# power.net
KiCad netlist of a schematic drawn in Altium Designer
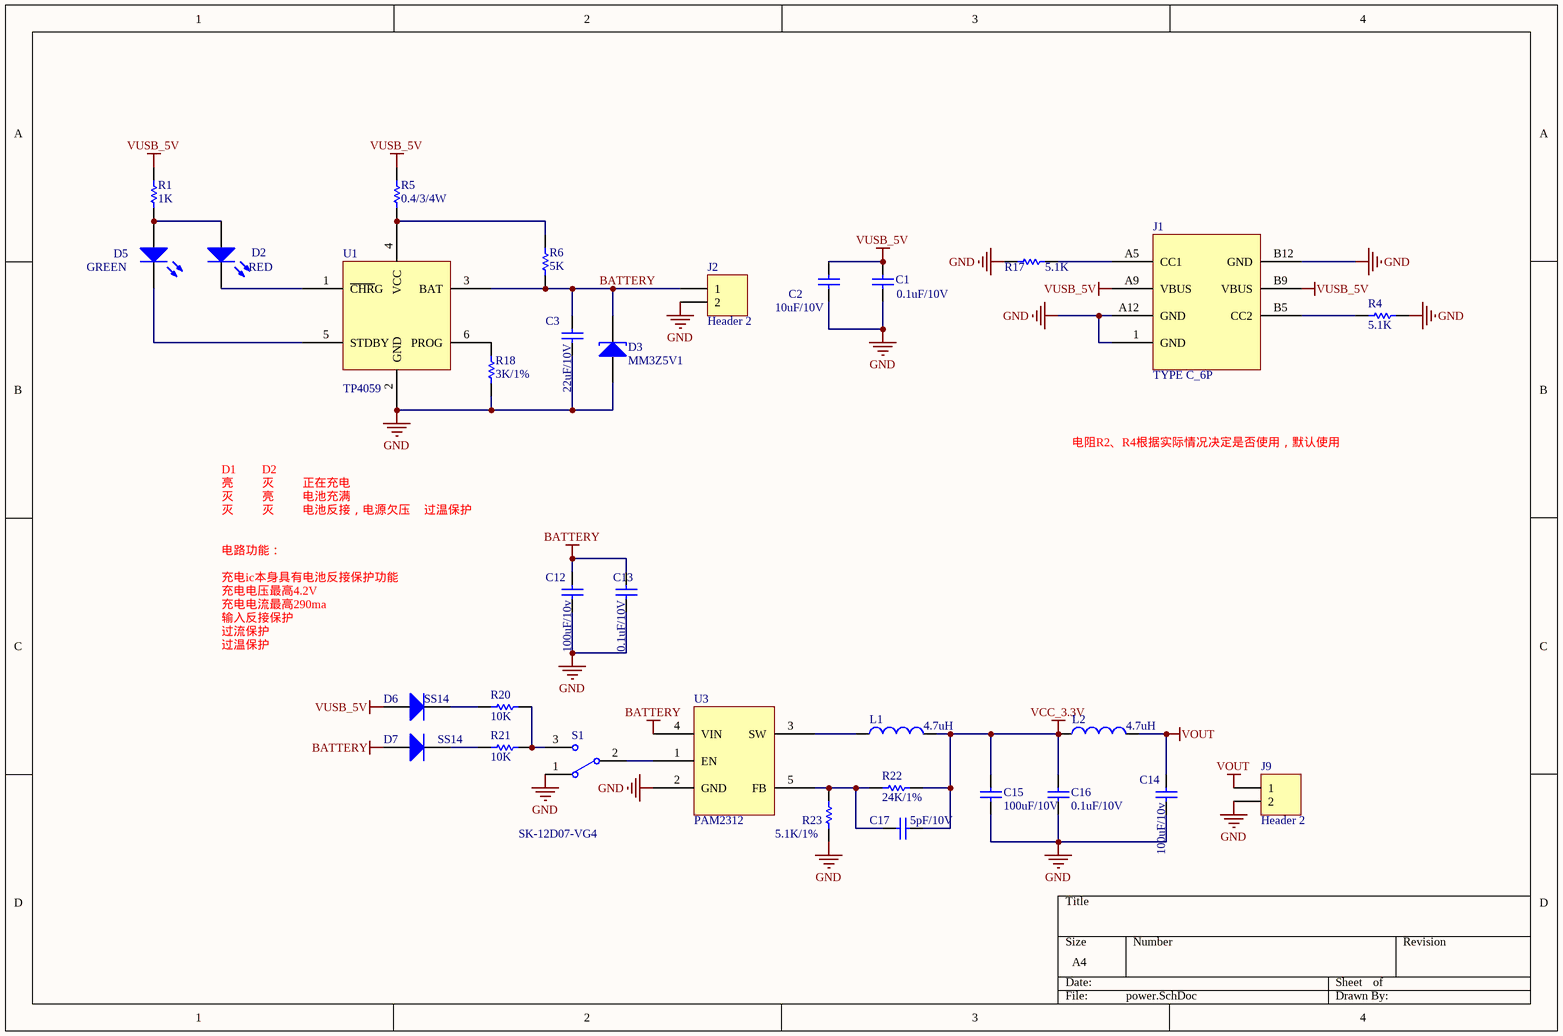
[diagram p0: power.SchDoc]

(export (version "E")
  (design (tool "Eeschema 10.0.6"))
  (components
    (comp (ref "C1")
      (value "0.1uF/10V")
      (footprint "0402C")
      (description "Capacitor")
      (fields (field (name "PUBLISHER") "Altium Limited"))
      (libsource (lib "Miscellaneous Devices") (part "Cap"))
    )
    (comp (ref "C2")
      (value "10uF/10V")
      (footprint "0603C")
      (description "Capacitor")
      (fields (field (name "PUBLISHER") "Altium Limited"))
      (libsource (lib "Miscellaneous Devices") (part "Cap"))
    )
    (comp (ref "C3")
      (value "22uF/10V")
      (footprint "1206C")
      (description "Capacitor")
      (fields (field (name "PUBLISHER") "Altium Limited"))
      (libsource (lib "Miscellaneous Devices") (part "Cap"))
    )
    (comp (ref "C12")
      (value "100uF/10v")
      (footprint "1206C")
      (description "Capacitor")
      (fields (field (name "PUBLISHER") "Altium Limited"))
      (libsource (lib "Miscellaneous Devices") (part "Cap"))
    )
    (comp (ref "C13")
      (value "0.1uF/10V")
      (footprint "0402c")
      (description "Capacitor")
      (fields (field (name "PUBLISHER") "Altium Limited"))
      (libsource (lib "Miscellaneous Devices") (part "Cap"))
    )
    (comp (ref "C14")
      (value "100uF/10v")
      (footprint "1206C")
      (description "Capacitor")
      (fields (field (name "PUBLISHER") "Altium Limited"))
      (libsource (lib "Miscellaneous Devices") (part "Cap"))
    )
    (comp (ref "C15")
      (value "100uF/10V")
      (footprint "1206C")
      (description "Capacitor")
      (fields (field (name "PUBLISHER") "Altium Limited"))
      (libsource (lib "Miscellaneous Devices") (part "Cap"))
    )
    (comp (ref "C16")
      (value "0.1uF/10V")
      (footprint "0402C")
      (description "Capacitor")
      (fields (field (name "PUBLISHER") "Altium Limited"))
      (libsource (lib "Miscellaneous Devices") (part "Cap"))
    )
    (comp (ref "C17")
      (value "5pF/10V")
      (footprint "0402C")
      (description "Capacitor")
      (fields (field (name "PUBLISHER") "Altium Limited"))
      (libsource (lib "Miscellaneous Devices") (part "Cap"))
    )
    (comp (ref "D2")
      (value "~")
      (footprint "0603LED")
      (description "Typical INFRARED GaAs LED")
      (fields (field (name "PUBLISHER") "RED"))
      (libsource (lib "Miscellaneous Devices") (part "LED0"))
    )
    (comp (ref "D3")
      (value "MM3Z5V1")
      (footprint "SOD323")
      (description "Tunnel Diode - RLC Model")
      (fields (field (name "PUBLISHER") "Altium Limited"))
      (libsource (lib "Miscellaneous Devices") (part "D Tunnel1"))
    )
    (comp (ref "D5")
      (value "~")
      (footprint "0603LED")
      (description "Typical INFRARED GaAs LED")
      (fields (field (name "PUBLISHER") "GREEN"))
      (libsource (lib "Miscellaneous Devices") (part "LED0"))
    )
    (comp (ref "D6")
      (value "SS14")
      (footprint "SMA")
      (description "Default Diode")
      (fields (field (name "PUBLISHER") "Altium Limited"))
      (libsource (lib "Miscellaneous Devices") (part "Diode"))
    )
    (comp (ref "D7")
      (value "SS14")
      (footprint "SMA")
      (description "Default Diode")
      (fields (field (name "PUBLISHER") "Altium Limited"))
      (libsource (lib "Miscellaneous Devices") (part "Diode"))
    )
    (comp (ref "J1")
      (value "TYPE C_6P")
      (footprint "TYPEC_6P")
      (libsource (lib "Schlib_20110825") (part "TYPE C_6P"))
    )
    (comp (ref "J2")
      (value "Header 2")
      (footprint "2X1.25MMZ")
      (description "Header, 2-Pin")
      (fields (field (name "PUBLISHER") "Altium Limited"))
      (libsource (lib "Miscellaneous Connectors") (part "Header 2"))
    )
    (comp (ref "J9")
      (value "Header 2")
      (footprint "HDR1X2")
      (description "Header, 2-Pin")
      (fields (field (name "PUBLISHER") "Altium Limited"))
      (libsource (lib "Miscellaneous Connectors") (part "Header 2"))
    )
    (comp (ref "L1")
      (value "4.7uH")
      (footprint "0805r")
      (description "Inductor")
      (fields (field (name "PUBLISHER") "Altium Limited"))
      (libsource (lib "Miscellaneous Devices") (part "Inductor"))
    )
    (comp (ref "L2")
      (value "4.7uH")
      (footprint "0805r")
      (description "Inductor")
      (fields (field (name "PUBLISHER") "Altium Limited"))
      (libsource (lib "Miscellaneous Devices") (part "Inductor"))
    )
    (comp (ref "R1")
      (value "1K")
      (footprint "0402R")
      (description "Semiconductor Resistor")
      (fields (field (name "PUBLISHER") "Altium Limited"))
      (libsource (lib "Miscellaneous Devices") (part "Res Semi"))
    )
    (comp (ref "R4")
      (value "5.1K")
      (footprint "0402R")
      (description "Semiconductor Resistor")
      (fields (field (name "PUBLISHER") "Altium Limited"))
      (libsource (lib "Miscellaneous Devices") (part "Res Semi"))
    )
    (comp (ref "R5")
      (value "0.4/3/4W")
      (footprint "2010R")
      (description "Semiconductor Resistor")
      (fields (field (name "PUBLISHER") "Altium Limited"))
      (libsource (lib "Miscellaneous Devices") (part "Res Semi"))
    )
    (comp (ref "R6")
      (value "5K")
      (footprint "0603R")
      (description "Semiconductor Resistor")
      (fields (field (name "PUBLISHER") "Altium Limited"))
      (libsource (lib "Miscellaneous Devices") (part "Res Semi"))
    )
    (comp (ref "R17")
      (value "5.1K")
      (footprint "0402R")
      (description "Semiconductor Resistor")
      (fields (field (name "PUBLISHER") "Altium Limited"))
      (libsource (lib "Miscellaneous Devices") (part "Res Semi"))
    )
    (comp (ref "R18")
      (value "3K/1%")
      (footprint "0402R")
      (description "Semiconductor Resistor")
      (fields (field (name "PUBLISHER") "Altium Limited"))
      (libsource (lib "Miscellaneous Devices") (part "Res Semi"))
    )
    (comp (ref "R20")
      (value "10K")
      (footprint "0402R")
      (description "Semiconductor Resistor")
      (fields (field (name "PUBLISHER") "Altium Limited"))
      (libsource (lib "Miscellaneous Devices") (part "Res Semi"))
    )
    (comp (ref "R21")
      (value "10K")
      (footprint "0402R")
      (description "Semiconductor Resistor")
      (fields (field (name "PUBLISHER") "Altium Limited"))
      (libsource (lib "Miscellaneous Devices") (part "Res Semi"))
    )
    (comp (ref "R22")
      (value "24K/1%")
      (footprint "0402R")
      (description "Semiconductor Resistor")
      (fields (field (name "PUBLISHER") "Altium Limited"))
      (libsource (lib "Miscellaneous Devices") (part "Res Semi"))
    )
    (comp (ref "R23")
      (value "5.1K/1%")
      (footprint "0402R")
      (description "Semiconductor Resistor")
      (fields (field (name "PUBLISHER") "Altium Limited"))
      (libsource (lib "Miscellaneous Devices") (part "Res Semi"))
    )
    (comp (ref "S1")
      (value "SK-12D07-VG4")
      (footprint "SK-12D07-VG4")
      (description "SPDT Subminiature Toggle Switch, Right Angle Mounting, Vertical Actuation")
      (fields (field (name "PUBLISHER") "Altium Limited"))
      (libsource (lib "Miscellaneous Devices") (part "SW-SPDT"))
    )
    (comp (ref "U1") (value "TP4059") (footprint "sot-23-6") (libsource (lib "CHARGER") (part "TP4059")))
    (comp (ref "U3")
      (value "PAM2312")
      (footprint "Pcblib_20110825:SOT-23-5")
      (libsource (lib "Schlib_20110825") (part "PAM2312"))
    )
  )
  (nets
    (net (code "1") (name "BATTERY") (class "Default")
      (node (ref "C12") (pin "1") (pinfunction "1_1") (pintype "passive"))
      (node (ref "C13") (pin "1") (pinfunction "1_1") (pintype "passive"))
      (node (ref "C3") (pin "1") (pinfunction "1_1") (pintype "passive"))
      (node (ref "D3") (pin "2") (pinfunction "K_2") (pintype "passive"))
      (node (ref "D7") (pin "1") (pinfunction "A_1") (pintype "passive"))
      (node (ref "J2") (pin "1") (pinfunction "1_1") (pintype "passive"))
      (node (ref "R6") (pin "1") (pinfunction "1_1") (pintype "passive"))
      (node (ref "U1") (pin "3") (pinfunction "BAT_3") (pintype "passive"))
      (node (ref "U3") (pin "4") (pinfunction "VIN_4") (pintype "passive"))
    )
    (net (code "2") (name "GND") (class "Default")
      (node (ref "C1") (pin "1") (pinfunction "1_1") (pintype "passive"))
      (node (ref "C12") (pin "2") (pinfunction "2_2") (pintype "passive"))
      (node (ref "C13") (pin "2") (pinfunction "2_2") (pintype "passive"))
      (node (ref "C14") (pin "2") (pinfunction "2_2") (pintype "passive"))
      (node (ref "C15") (pin "1") (pinfunction "1_1") (pintype "passive"))
      (node (ref "C16") (pin "1") (pinfunction "1_1") (pintype "passive"))
      (node (ref "C2") (pin "1") (pinfunction "1_1") (pintype "passive"))
      (node (ref "C3") (pin "2") (pinfunction "2_2") (pintype "passive"))
      (node (ref "D3") (pin "1") (pinfunction "A_1") (pintype "passive"))
      (node (ref "J1") (pin "1") (pinfunction "GND_1") (pintype "passive"))
      (node (ref "J1") (pin "A12") (pinfunction "GND_A12") (pintype "passive"))
      (node (ref "J1") (pin "B12") (pinfunction "GND_B12") (pintype "passive"))
      (node (ref "J2") (pin "2") (pinfunction "2_2") (pintype "passive"))
      (node (ref "J9") (pin "2") (pinfunction "2_2") (pintype "passive"))
      (node (ref "R17") (pin "2") (pinfunction "2_2") (pintype "passive"))
      (node (ref "R18") (pin "1") (pinfunction "1_1") (pintype "passive"))
      (node (ref "R23") (pin "1") (pinfunction "1_1") (pintype "passive"))
      (node (ref "R4") (pin "2") (pinfunction "2_2") (pintype "passive"))
      (node (ref "S1") (pin "1") (pinfunction "1_1") (pintype "passive"))
      (node (ref "U1") (pin "2") (pinfunction "GND_2") (pintype "passive"))
      (node (ref "U3") (pin "2") (pinfunction "GND_2") (pintype "passive"))
    )
    (net (code "3") (name "Net-(D2-A)") (class "Default")
      (node (ref "D2") (pin "1") (pinfunction "A_1") (pintype "passive"))
      (node (ref "D5") (pin "1") (pinfunction "A_1") (pintype "passive"))
      (node (ref "R1") (pin "1") (pinfunction "1_1") (pintype "passive"))
    )
    (net (code "4") (name "Net-(D2-K)") (class "Default")
      (node (ref "D2") (pin "2") (pinfunction "K_2") (pintype "passive"))
      (node (ref "U1") (pin "1") (pinfunction "~{CHR}G_1") (pintype "passive"))
    )
    (net (code "5") (name "Net-(D5-K)") (class "Default")
      (node (ref "D5") (pin "2") (pinfunction "K_2") (pintype "passive"))
      (node (ref "U1") (pin "5") (pinfunction "STDBY_5") (pintype "passive"))
    )
    (net (code "6") (name "Net-(D6-K)") (class "Default")
      (node (ref "D6") (pin "2") (pinfunction "K_2") (pintype "passive"))
      (node (ref "R20") (pin "1") (pinfunction "1_1") (pintype "passive"))
    )
    (net (code "7") (name "Net-(D7-K)") (class "Default")
      (node (ref "D7") (pin "2") (pinfunction "K_2") (pintype "passive"))
      (node (ref "R21") (pin "1") (pinfunction "1_1") (pintype "passive"))
    )
    (net (code "8") (name "Net-(J1-CC1)") (class "Default")
      (node (ref "J1") (pin "A5") (pinfunction "CC1_A5") (pintype "passive"))
      (node (ref "R17") (pin "1") (pinfunction "1_1") (pintype "passive"))
    )
    (net (code "9") (name "Net-(J1-CC2)") (class "Default")
      (node (ref "J1") (pin "B5") (pinfunction "CC2_B5") (pintype "passive"))
      (node (ref "R4") (pin "1") (pinfunction "1_1") (pintype "passive"))
    )
    (net (code "10") (name "Net-(R20-Pad2)") (class "Default")
      (node (ref "R20") (pin "2") (pinfunction "2_2") (pintype "passive"))
      (node (ref "R21") (pin "2") (pinfunction "2_2") (pintype "passive"))
      (node (ref "S1") (pin "3") (pinfunction "3_3") (pintype "passive"))
    )
    (net (code "11") (name "Net-(U1-PROG)") (class "Default")
      (node (ref "R18") (pin "2") (pinfunction "2_2") (pintype "passive"))
      (node (ref "U1") (pin "6") (pinfunction "PROG_6") (pintype "passive"))
    )
    (net (code "12") (name "Net-(U1-VCC)") (class "Default")
      (node (ref "R5") (pin "2") (pinfunction "2_2") (pintype "passive"))
      (node (ref "R6") (pin "2") (pinfunction "2_2") (pintype "passive"))
      (node (ref "U1") (pin "4") (pinfunction "VCC_4") (pintype "passive"))
    )
    (net (code "13") (name "Net-(U3-EN)") (class "Default")
      (node (ref "S1") (pin "2") (pinfunction "2_2") (pintype "passive"))
      (node (ref "U3") (pin "1") (pinfunction "EN_1") (pintype "passive"))
    )
    (net (code "14") (name "Net-(U3-FB)") (class "Default")
      (node (ref "C17") (pin "1") (pinfunction "1_1") (pintype "passive"))
      (node (ref "R22") (pin "1") (pinfunction "1_1") (pintype "passive"))
      (node (ref "R23") (pin "2") (pinfunction "2_2") (pintype "passive"))
      (node (ref "U3") (pin "5") (pinfunction "FB_5") (pintype "passive"))
    )
    (net (code "15") (name "Net-(U3-SW)") (class "Default")
      (node (ref "L1") (pin "1") (pinfunction "1_1") (pintype "passive"))
      (node (ref "U3") (pin "3") (pinfunction "SW_3") (pintype "passive"))
    )
    (net (code "16") (name "VCC_3.3V") (class "Default")
      (node (ref "C15") (pin "2") (pinfunction "2_2") (pintype "passive"))
      (node (ref "C16") (pin "2") (pinfunction "2_2") (pintype "passive"))
      (node (ref "C17") (pin "2") (pinfunction "2_2") (pintype "passive"))
      (node (ref "L1") (pin "2") (pinfunction "2_2") (pintype "passive"))
      (node (ref "L2") (pin "1") (pinfunction "1_1") (pintype "passive"))
      (node (ref "R22") (pin "2") (pinfunction "2_2") (pintype "passive"))
    )
    (net (code "17") (name "VOUT") (class "Default")
      (node (ref "C14") (pin "1") (pinfunction "1_1") (pintype "passive"))
      (node (ref "J9") (pin "1") (pinfunction "1_1") (pintype "passive"))
      (node (ref "L2") (pin "2") (pinfunction "2_2") (pintype "passive"))
    )
    (net (code "18") (name "VUSB_5V") (class "Default")
      (node (ref "C1") (pin "2") (pinfunction "2_2") (pintype "passive"))
      (node (ref "C2") (pin "2") (pinfunction "2_2") (pintype "passive"))
      (node (ref "D6") (pin "1") (pinfunction "A_1") (pintype "passive"))
      (node (ref "J1") (pin "A9") (pinfunction "VBUS_A9") (pintype "passive"))
      (node (ref "J1") (pin "B9") (pinfunction "VBUS_B9") (pintype "passive"))
      (node (ref "R1") (pin "2") (pinfunction "2_2") (pintype "passive"))
      (node (ref "R5") (pin "1") (pinfunction "1_1") (pintype "passive"))
    )
  )
)
